# Voltage_Shifters.net
KiCad netlist of a schematic drawn in Altium Designer
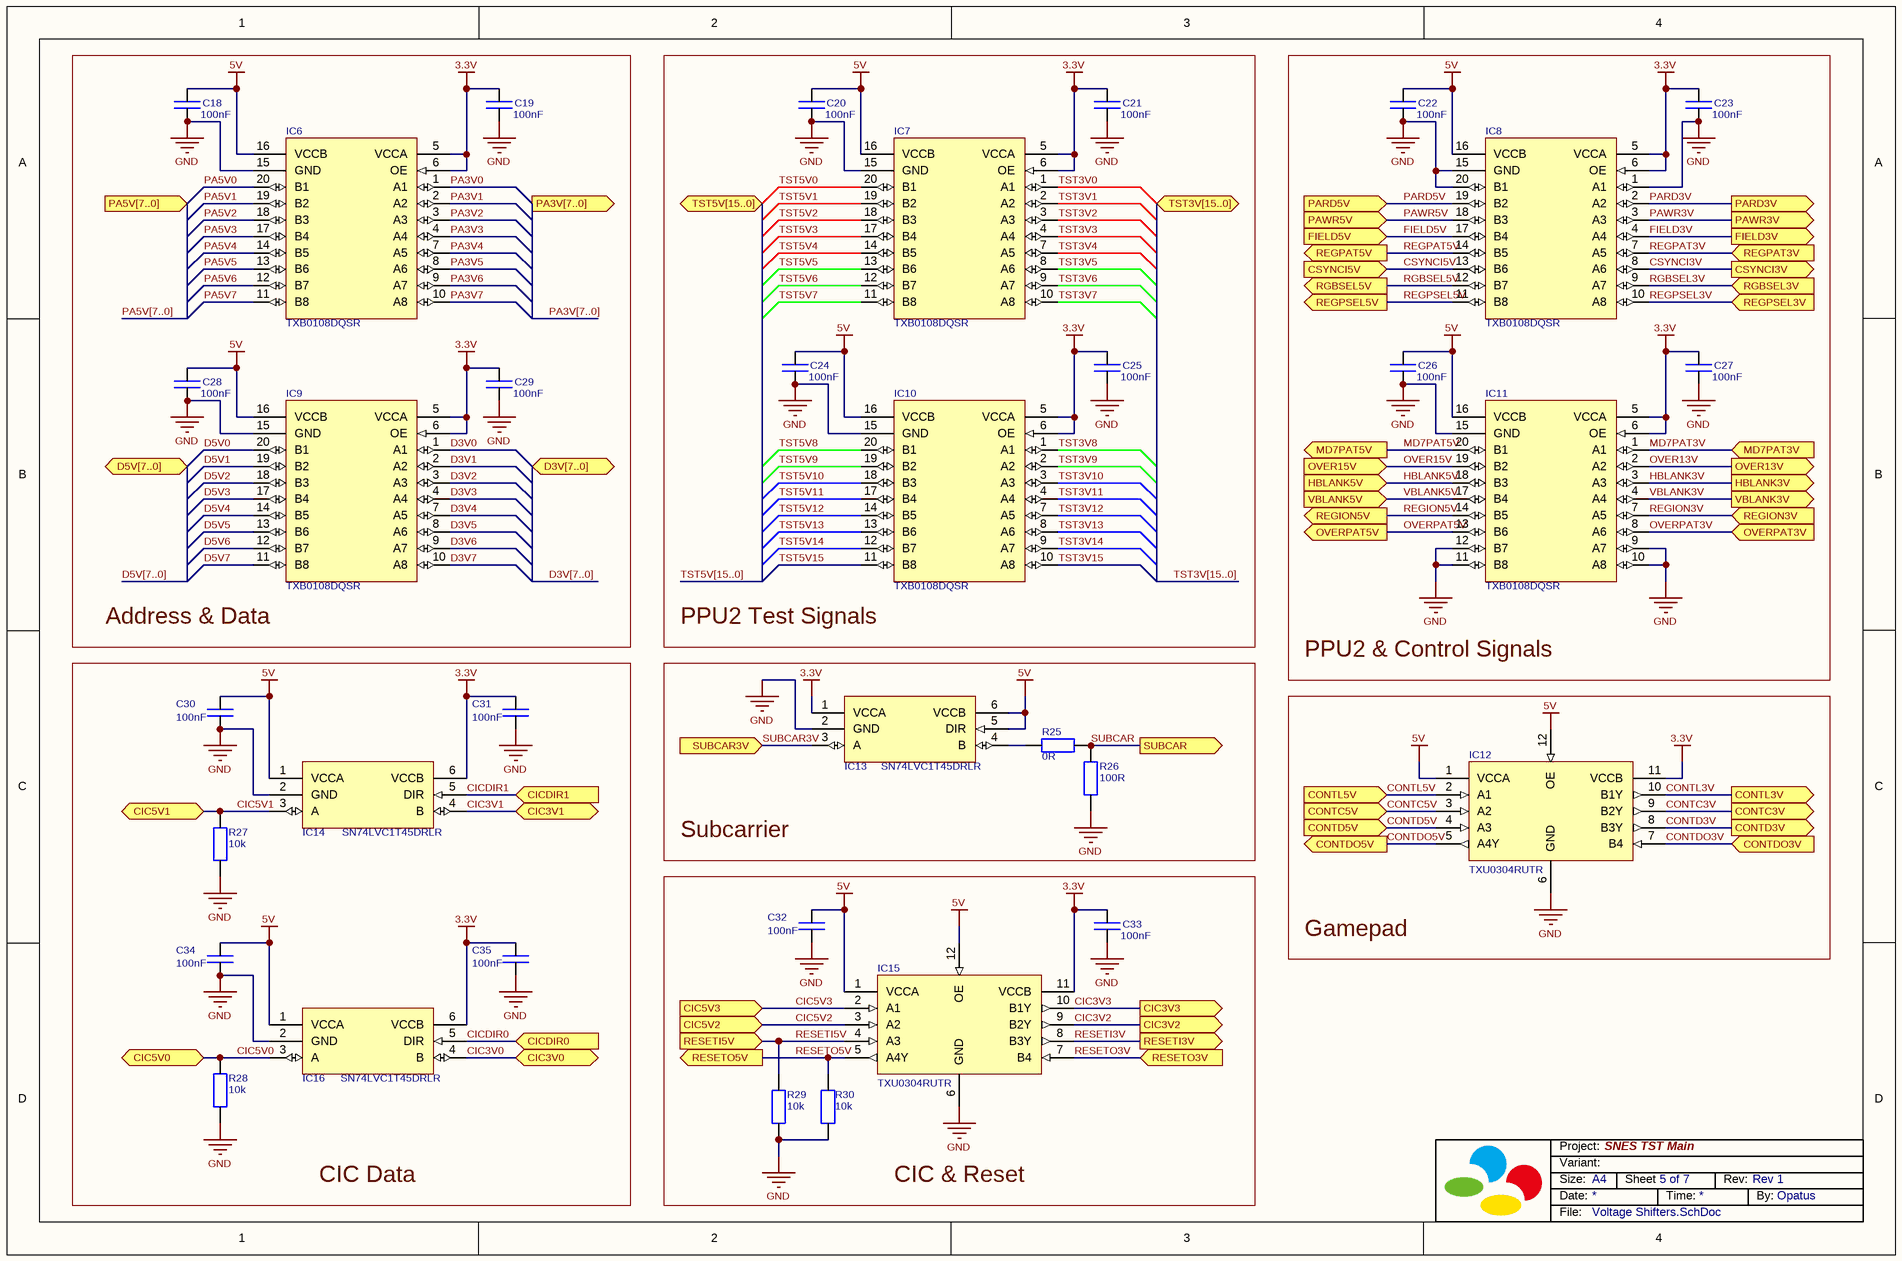
[diagram p0: Voltage Shifters.SchDoc]

(export (version "E")
  (design (tool "Eeschema 10.0.6"))
  (components
    (comp (ref "C18")
      (value "100nF")
      (footprint "Cap_0402_Chip")
      (fields
        (field (name "TOLERANCE") "±20%")
        (field (name "Comment") "Ceramic Capacitor 100nF 10V ±20% X7R 0402")
      )
      (libsource (lib "PCB") (part "Capacitor"))
    )
    (comp (ref "C19")
      (value "100nF")
      (footprint "Cap_0402_Chip")
      (fields
        (field (name "TOLERANCE") "±20%")
        (field (name "Comment") "Ceramic Capacitor 100nF 10V ±20% X7R 0402")
      )
      (libsource (lib "PCB") (part "Capacitor"))
    )
    (comp (ref "C20")
      (value "100nF")
      (footprint "Cap_0402_Chip")
      (fields
        (field (name "TOLERANCE") "±20%")
        (field (name "Comment") "Ceramic Capacitor 100nF 10V ±20% X7R 0402")
      )
      (libsource (lib "PCB") (part "Capacitor"))
    )
    (comp (ref "C21")
      (value "100nF")
      (footprint "Cap_0402_Chip")
      (fields
        (field (name "TOLERANCE") "±20%")
        (field (name "Comment") "Ceramic Capacitor 100nF 10V ±20% X7R 0402")
      )
      (libsource (lib "PCB") (part "Capacitor"))
    )
    (comp (ref "C22")
      (value "100nF")
      (footprint "Cap_0402_Chip")
      (fields
        (field (name "TOLERANCE") "±20%")
        (field (name "Comment") "Ceramic Capacitor 100nF 10V ±20% X7R 0402")
      )
      (libsource (lib "PCB") (part "Capacitor"))
    )
    (comp (ref "C23")
      (value "100nF")
      (footprint "Cap_0402_Chip")
      (fields
        (field (name "TOLERANCE") "±20%")
        (field (name "Comment") "Ceramic Capacitor 100nF 10V ±20% X7R 0402")
      )
      (libsource (lib "PCB") (part "Capacitor"))
    )
    (comp (ref "C24")
      (value "100nF")
      (footprint "Cap_0402_Chip")
      (fields
        (field (name "TOLERANCE") "±20%")
        (field (name "Comment") "Ceramic Capacitor 100nF 10V ±20% X7R 0402")
      )
      (libsource (lib "PCB") (part "Capacitor"))
    )
    (comp (ref "C25")
      (value "100nF")
      (footprint "Cap_0402_Chip")
      (fields
        (field (name "TOLERANCE") "±20%")
        (field (name "Comment") "Ceramic Capacitor 100nF 10V ±20% X7R 0402")
      )
      (libsource (lib "PCB") (part "Capacitor"))
    )
    (comp (ref "C26")
      (value "100nF")
      (footprint "Cap_0402_Chip")
      (fields
        (field (name "TOLERANCE") "±20%")
        (field (name "Comment") "Ceramic Capacitor 100nF 10V ±20% X7R 0402")
      )
      (libsource (lib "PCB") (part "Capacitor"))
    )
    (comp (ref "C27")
      (value "100nF")
      (footprint "Cap_0402_Chip")
      (fields
        (field (name "TOLERANCE") "±20%")
        (field (name "Comment") "Ceramic Capacitor 100nF 10V ±20% X7R 0402")
      )
      (libsource (lib "PCB") (part "Capacitor"))
    )
    (comp (ref "C28")
      (value "100nF")
      (footprint "Cap_0402_Chip")
      (fields
        (field (name "TOLERANCE") "±20%")
        (field (name "Comment") "Ceramic Capacitor 100nF 10V ±20% X7R 0402")
      )
      (libsource (lib "PCB") (part "Capacitor"))
    )
    (comp (ref "C29")
      (value "100nF")
      (footprint "Cap_0402_Chip")
      (fields
        (field (name "TOLERANCE") "±20%")
        (field (name "Comment") "Ceramic Capacitor 100nF 10V ±20% X7R 0402")
      )
      (libsource (lib "PCB") (part "Capacitor"))
    )
    (comp (ref "C30")
      (value "100nF")
      (footprint "Cap_0402_Chip")
      (fields
        (field (name "TOLERANCE") "±20%")
        (field (name "Comment") "Ceramic Capacitor 100nF 10V ±20% X7R 0402")
      )
      (libsource (lib "PCB") (part "Capacitor"))
    )
    (comp (ref "C31")
      (value "100nF")
      (footprint "Cap_0402_Chip")
      (fields
        (field (name "TOLERANCE") "±20%")
        (field (name "Comment") "Ceramic Capacitor 100nF 10V ±20% X7R 0402")
      )
      (libsource (lib "PCB") (part "Capacitor"))
    )
    (comp (ref "C32")
      (value "100nF")
      (footprint "Cap_0402_Chip")
      (fields
        (field (name "TOLERANCE") "±20%")
        (field (name "Comment") "Ceramic Capacitor 100nF 10V ±20% X7R 0402")
      )
      (libsource (lib "PCB") (part "Capacitor"))
    )
    (comp (ref "C33")
      (value "100nF")
      (footprint "Cap_0402_Chip")
      (fields
        (field (name "TOLERANCE") "±20%")
        (field (name "Comment") "Ceramic Capacitor 100nF 10V ±20% X7R 0402")
      )
      (libsource (lib "PCB") (part "Capacitor"))
    )
    (comp (ref "C34")
      (value "100nF")
      (footprint "Cap_0402_Chip")
      (fields
        (field (name "TOLERANCE") "±20%")
        (field (name "Comment") "Ceramic Capacitor 100nF 10V ±20% X7R 0402")
      )
      (libsource (lib "PCB") (part "Capacitor"))
    )
    (comp (ref "C35")
      (value "100nF")
      (footprint "Cap_0402_Chip")
      (fields
        (field (name "TOLERANCE") "±20%")
        (field (name "Comment") "Ceramic Capacitor 100nF 10V ±20% X7R 0402")
      )
      (libsource (lib "PCB") (part "Capacitor"))
    )
    (comp (ref "IC6")
      (value "TXB0108DQSR")
      (footprint "SON20")
      (description "8-bit level shifter")
      (fields
        (field (name "MANUFACTURER") "Texas Instruments")
        (field (name "MANUFACTURER_PART_NUMBER") "TXB0108DQSR")
      )
      (libsource (lib "PCB") (part "TXB0108DQSR"))
    )
    (comp (ref "IC7")
      (value "TXB0108DQSR")
      (footprint "SON20")
      (description "8-bit level shifter")
      (fields
        (field (name "MANUFACTURER") "Texas Instruments")
        (field (name "MANUFACTURER_PART_NUMBER") "TXB0108DQSR")
      )
      (libsource (lib "PCB") (part "TXB0108DQSR"))
    )
    (comp (ref "IC8")
      (value "TXB0108DQSR")
      (footprint "SON20")
      (description "8-bit level shifter")
      (fields
        (field (name "MANUFACTURER") "Texas Instruments")
        (field (name "MANUFACTURER_PART_NUMBER") "TXB0108DQSR")
      )
      (libsource (lib "PCB") (part "TXB0108DQSR"))
    )
    (comp (ref "IC9")
      (value "TXB0108DQSR")
      (footprint "SON20")
      (description "8-bit level shifter")
      (fields
        (field (name "MANUFACTURER") "Texas Instruments")
        (field (name "MANUFACTURER_PART_NUMBER") "TXB0108DQSR")
      )
      (libsource (lib "PCB") (part "TXB0108DQSR"))
    )
    (comp (ref "IC10")
      (value "TXB0108DQSR")
      (footprint "SON20")
      (description "8-bit level shifter")
      (fields
        (field (name "MANUFACTURER") "Texas Instruments")
        (field (name "MANUFACTURER_PART_NUMBER") "TXB0108DQSR")
      )
      (libsource (lib "PCB") (part "TXB0108DQSR"))
    )
    (comp (ref "IC11")
      (value "TXB0108DQSR")
      (footprint "SON20")
      (description "8-bit level shifter")
      (fields
        (field (name "MANUFACTURER") "Texas Instruments")
        (field (name "MANUFACTURER_PART_NUMBER") "TXB0108DQSR")
      )
      (libsource (lib "PCB") (part "TXB0108DQSR"))
    )
    (comp (ref "IC12")
      (value "TXU0304")
      (footprint "UQFN12")
      (description "4-bit level shifter")
      (fields
        (field (name "MANUFACTURER") "Texas Instruments")
        (field (name "MANUFACTURER_PART_NUMBER") "TXU0304RUTR")
      )
      (libsource (lib "PCB") (part "TXU0304"))
    )
    (comp (ref "IC13")
      (value "SN74LVC1T45")
      (footprint "SOT-5X3")
      (description "1-bit Transceiver")
      (fields
        (field (name "MANUFACTURER") "Texas Instruments")
        (field (name "MANUFACTURER_PART_NUMBER") "SN74LVC1T45DRLR")
      )
      (libsource (lib "PCB") (part "SN74LVC1T45"))
    )
    (comp (ref "IC14")
      (value "SN74LVC1T45")
      (footprint "SOT-5X3")
      (description "1-bit Transceiver")
      (fields
        (field (name "MANUFACTURER") "Texas Instruments")
        (field (name "MANUFACTURER_PART_NUMBER") "SN74LVC1T45DRLR")
      )
      (libsource (lib "PCB") (part "SN74LVC1T45"))
    )
    (comp (ref "IC15")
      (value "TXU0304")
      (footprint "UQFN12")
      (description "4-bit level shifter")
      (fields
        (field (name "MANUFACTURER") "Texas Instruments")
        (field (name "MANUFACTURER_PART_NUMBER") "TXU0304RUTR")
      )
      (libsource (lib "PCB") (part "TXU0304"))
    )
    (comp (ref "IC16")
      (value "SN74LVC1T45")
      (footprint "SOT-5X3")
      (description "1-bit Transceiver")
      (fields
        (field (name "MANUFACTURER") "Texas Instruments")
        (field (name "MANUFACTURER_PART_NUMBER") "SN74LVC1T45DRLR")
      )
      (libsource (lib "PCB") (part "SN74LVC1T45"))
    )
    (comp (ref "R25")
      (value "0R")
      (footprint "Res_0603_Chip")
      (fields (field (name "TOLERANCE") "±1%") (field (name "Comment") "Resistor 0R 0603 ±1%"))
      (libsource (lib "") (part "R_2"))
    )
    (comp (ref "R26")
      (value "100R")
      (footprint "Res_0603_Chip")
      (fields (field (name "TOLERANCE") "±1%") (field (name "Comment") "Resistor 100R 0603 ±1%"))
      (libsource (lib "") (part "R_1"))
    )
    (comp (ref "R27")
      (value "10k")
      (footprint "Res_0402_Chip")
      (fields (field (name "TOLERANCE") "±1%") (field (name "Comment") "Resistor 10k 0402 ±1%"))
      (libsource (lib "PCB") (part "R"))
    )
    (comp (ref "R28")
      (value "10k")
      (footprint "Res_0402_Chip")
      (fields (field (name "TOLERANCE") "±1%") (field (name "Comment") "Resistor 10k 0402 ±1%"))
      (libsource (lib "PCB") (part "R"))
    )
    (comp (ref "R29")
      (value "10k")
      (footprint "Res_0402_Chip")
      (fields (field (name "TOLERANCE") "±1%") (field (name "Comment") "Resistor 10k 0402 ±1%"))
      (libsource (lib "") (part "R_1"))
    )
    (comp (ref "R30")
      (value "10k")
      (footprint "Res_0402_Chip")
      (fields (field (name "TOLERANCE") "±1%") (field (name "Comment") "Resistor 10k 0402 ±1%"))
      (libsource (lib "PCB") (part "R"))
    )
  )
  (nets
    (net (code "1") (name "/CIC3V0") (class "Default")
      (node (ref "IC16") (pin "4") (pinfunction "B_4") (pintype "bidirectional"))
    )
    (net (code "2") (name "/CIC3V1") (class "Default")
      (node (ref "IC14") (pin "4") (pinfunction "B_4") (pintype "bidirectional"))
    )
    (net (code "3") (name "/CIC3V2") (class "Default")
      (node (ref "IC15") (pin "9") (pinfunction "B2Y_9") (pintype "output"))
    )
    (net (code "4") (name "/CIC3V3") (class "Default")
      (node (ref "IC15") (pin "10") (pinfunction "B1Y_10") (pintype "output"))
    )
    (net (code "5") (name "/CIC5V0") (class "Default")
      (node (ref "IC16") (pin "3") (pinfunction "A_3") (pintype "bidirectional"))
      (node (ref "R28") (pin "2") (pintype "passive"))
    )
    (net (code "6") (name "/CIC5V1") (class "Default")
      (node (ref "IC14") (pin "3") (pinfunction "A_3") (pintype "bidirectional"))
      (node (ref "R27") (pin "2") (pintype "passive"))
    )
    (net (code "7") (name "/CIC5V2") (class "Default")
      (node (ref "IC15") (pin "3") (pinfunction "A2_3") (pintype "input"))
    )
    (net (code "8") (name "/CIC5V3") (class "Default")
      (node (ref "IC15") (pin "2") (pinfunction "A1_2") (pintype "input"))
    )
    (net (code "9") (name "/CICDIR0") (class "Default")
      (node (ref "IC16") (pin "5") (pinfunction "DIR_5") (pintype "input"))
    )
    (net (code "10") (name "/CICDIR1") (class "Default")
      (node (ref "IC14") (pin "5") (pinfunction "DIR_5") (pintype "input"))
    )
    (net (code "11") (name "/CONTC3V") (class "Default")
      (node (ref "IC12") (pin "9") (pinfunction "B2Y_9") (pintype "output"))
    )
    (net (code "12") (name "/CONTC5V") (class "Default")
      (node (ref "IC12") (pin "3") (pinfunction "A2_3") (pintype "input"))
    )
    (net (code "13") (name "/CONTD3V") (class "Default")
      (node (ref "IC12") (pin "8") (pinfunction "B3Y_8") (pintype "output"))
    )
    (net (code "14") (name "/CONTD5V") (class "Default")
      (node (ref "IC12") (pin "4") (pinfunction "A3_4") (pintype "input"))
    )
    (net (code "15") (name "/CONTDO3V") (class "Default")
      (node (ref "IC12") (pin "7") (pinfunction "B4_7") (pintype "input"))
    )
    (net (code "16") (name "/CONTDO5V") (class "Default")
      (node (ref "IC12") (pin "5") (pinfunction "A4Y_5") (pintype "output"))
    )
    (net (code "17") (name "/CONTL3V") (class "Default")
      (node (ref "IC12") (pin "10") (pinfunction "B1Y_10") (pintype "output"))
    )
    (net (code "18") (name "/CONTL5V") (class "Default")
      (node (ref "IC12") (pin "2") (pinfunction "A1_2") (pintype "input"))
    )
    (net (code "19") (name "/CSYNCI3V") (class "Default")
      (node (ref "IC8") (pin "8") (pinfunction "A6_8") (pintype "bidirectional"))
    )
    (net (code "20") (name "/CSYNCI5V") (class "Default")
      (node (ref "IC8") (pin "13") (pinfunction "B6_13") (pintype "bidirectional"))
    )
    (net (code "21") (name "/D3V0") (class "Default")
      (node (ref "IC9") (pin "1") (pinfunction "A1_1") (pintype "bidirectional"))
    )
    (net (code "22") (name "/D3V1") (class "Default")
      (node (ref "IC9") (pin "2") (pinfunction "A2_2") (pintype "bidirectional"))
    )
    (net (code "23") (name "/D3V2") (class "Default")
      (node (ref "IC9") (pin "3") (pinfunction "A3_3") (pintype "bidirectional"))
    )
    (net (code "24") (name "/D3V3") (class "Default")
      (node (ref "IC9") (pin "4") (pinfunction "A4_4") (pintype "bidirectional"))
    )
    (net (code "25") (name "/D3V4") (class "Default")
      (node (ref "IC9") (pin "7") (pinfunction "A5_7") (pintype "bidirectional"))
    )
    (net (code "26") (name "/D3V5") (class "Default")
      (node (ref "IC9") (pin "8") (pinfunction "A6_8") (pintype "bidirectional"))
    )
    (net (code "27") (name "/D3V6") (class "Default")
      (node (ref "IC9") (pin "9") (pinfunction "A7_9") (pintype "bidirectional"))
    )
    (net (code "28") (name "/D3V7") (class "Default")
      (node (ref "IC9") (pin "10") (pinfunction "A8_10") (pintype "bidirectional"))
    )
    (net (code "30") (name "/D5V0") (class "Default")
      (node (ref "IC9") (pin "20") (pinfunction "B1_20") (pintype "bidirectional"))
    )
    (net (code "31") (name "/D5V1") (class "Default")
      (node (ref "IC9") (pin "19") (pinfunction "B2_19") (pintype "bidirectional"))
    )
    (net (code "32") (name "/D5V2") (class "Default")
      (node (ref "IC9") (pin "18") (pinfunction "B3_18") (pintype "bidirectional"))
    )
    (net (code "33") (name "/D5V3") (class "Default")
      (node (ref "IC9") (pin "17") (pinfunction "B4_17") (pintype "bidirectional"))
    )
    (net (code "34") (name "/D5V4") (class "Default")
      (node (ref "IC9") (pin "14") (pinfunction "B5_14") (pintype "bidirectional"))
    )
    (net (code "35") (name "/D5V5") (class "Default")
      (node (ref "IC9") (pin "13") (pinfunction "B6_13") (pintype "bidirectional"))
    )
    (net (code "36") (name "/D5V6") (class "Default")
      (node (ref "IC9") (pin "12") (pinfunction "B7_12") (pintype "bidirectional"))
    )
    (net (code "37") (name "/D5V7") (class "Default")
      (node (ref "IC9") (pin "11") (pinfunction "B8_11") (pintype "bidirectional"))
    )
    (net (code "39") (name "/FIELD3V") (class "Default")
      (node (ref "IC8") (pin "4") (pinfunction "A4_4") (pintype "bidirectional"))
    )
    (net (code "40") (name "/FIELD5V") (class "Default")
      (node (ref "IC8") (pin "17") (pinfunction "B4_17") (pintype "bidirectional"))
    )
    (net (code "41") (name "/HBLANK3V") (class "Default")
      (node (ref "IC11") (pin "3") (pinfunction "A3_3") (pintype "bidirectional"))
    )
    (net (code "42") (name "/HBLANK5V") (class "Default")
      (node (ref "IC11") (pin "18") (pinfunction "B3_18") (pintype "bidirectional"))
    )
    (net (code "43") (name "/MD7PAT3V") (class "Default")
      (node (ref "IC11") (pin "1") (pinfunction "A1_1") (pintype "bidirectional"))
    )
    (net (code "44") (name "/MD7PAT5V") (class "Default")
      (node (ref "IC11") (pin "20") (pinfunction "B1_20") (pintype "bidirectional"))
    )
    (net (code "45") (name "/OVER13V") (class "Default")
      (node (ref "IC11") (pin "2") (pinfunction "A2_2") (pintype "bidirectional"))
    )
    (net (code "46") (name "/OVER15V") (class "Default")
      (node (ref "IC11") (pin "19") (pinfunction "B2_19") (pintype "bidirectional"))
    )
    (net (code "47") (name "/OVERPAT3V") (class "Default")
      (node (ref "IC11") (pin "8") (pinfunction "A6_8") (pintype "bidirectional"))
    )
    (net (code "48") (name "/OVERPAT5V") (class "Default")
      (node (ref "IC11") (pin "13") (pinfunction "B6_13") (pintype "bidirectional"))
    )
    (net (code "49") (name "/PA3V0") (class "Default")
      (node (ref "IC6") (pin "1") (pinfunction "A1_1") (pintype "bidirectional"))
    )
    (net (code "50") (name "/PA3V1") (class "Default")
      (node (ref "IC6") (pin "2") (pinfunction "A2_2") (pintype "bidirectional"))
    )
    (net (code "51") (name "/PA3V2") (class "Default")
      (node (ref "IC6") (pin "3") (pinfunction "A3_3") (pintype "bidirectional"))
    )
    (net (code "52") (name "/PA3V3") (class "Default")
      (node (ref "IC6") (pin "4") (pinfunction "A4_4") (pintype "bidirectional"))
    )
    (net (code "53") (name "/PA3V4") (class "Default")
      (node (ref "IC6") (pin "7") (pinfunction "A5_7") (pintype "bidirectional"))
    )
    (net (code "54") (name "/PA3V5") (class "Default")
      (node (ref "IC6") (pin "8") (pinfunction "A6_8") (pintype "bidirectional"))
    )
    (net (code "55") (name "/PA3V6") (class "Default")
      (node (ref "IC6") (pin "9") (pinfunction "A7_9") (pintype "bidirectional"))
    )
    (net (code "56") (name "/PA3V7") (class "Default")
      (node (ref "IC6") (pin "10") (pinfunction "A8_10") (pintype "bidirectional"))
    )
    (net (code "58") (name "/PA5V0") (class "Default")
      (node (ref "IC6") (pin "20") (pinfunction "B1_20") (pintype "bidirectional"))
    )
    (net (code "59") (name "/PA5V1") (class "Default")
      (node (ref "IC6") (pin "19") (pinfunction "B2_19") (pintype "bidirectional"))
    )
    (net (code "60") (name "/PA5V2") (class "Default")
      (node (ref "IC6") (pin "18") (pinfunction "B3_18") (pintype "bidirectional"))
    )
    (net (code "61") (name "/PA5V3") (class "Default")
      (node (ref "IC6") (pin "17") (pinfunction "B4_17") (pintype "bidirectional"))
    )
    (net (code "62") (name "/PA5V4") (class "Default")
      (node (ref "IC6") (pin "14") (pinfunction "B5_14") (pintype "bidirectional"))
    )
    (net (code "63") (name "/PA5V5") (class "Default")
      (node (ref "IC6") (pin "13") (pinfunction "B6_13") (pintype "bidirectional"))
    )
    (net (code "64") (name "/PA5V6") (class "Default")
      (node (ref "IC6") (pin "12") (pinfunction "B7_12") (pintype "bidirectional"))
    )
    (net (code "65") (name "/PA5V7") (class "Default")
      (node (ref "IC6") (pin "11") (pinfunction "B8_11") (pintype "bidirectional"))
    )
    (net (code "67") (name "/PARD3V") (class "Default")
      (node (ref "IC8") (pin "2") (pinfunction "A2_2") (pintype "bidirectional"))
    )
    (net (code "68") (name "/PARD5V") (class "Default")
      (node (ref "IC8") (pin "19") (pinfunction "B2_19") (pintype "bidirectional"))
    )
    (net (code "69") (name "/PAWR3V") (class "Default")
      (node (ref "IC8") (pin "3") (pinfunction "A3_3") (pintype "bidirectional"))
    )
    (net (code "70") (name "/PAWR5V") (class "Default")
      (node (ref "IC8") (pin "18") (pinfunction "B3_18") (pintype "bidirectional"))
    )
    (net (code "71") (name "/REGION3V") (class "Default")
      (node (ref "IC11") (pin "7") (pinfunction "A5_7") (pintype "bidirectional"))
    )
    (net (code "72") (name "/REGION5V") (class "Default")
      (node (ref "IC11") (pin "14") (pinfunction "B5_14") (pintype "bidirectional"))
    )
    (net (code "73") (name "/REGPAT3V") (class "Default")
      (node (ref "IC8") (pin "7") (pinfunction "A5_7") (pintype "bidirectional"))
    )
    (net (code "74") (name "/REGPAT5V") (class "Default")
      (node (ref "IC8") (pin "14") (pinfunction "B5_14") (pintype "bidirectional"))
    )
    (net (code "75") (name "/REGPSEL3V") (class "Default")
      (node (ref "IC8") (pin "10") (pinfunction "A8_10") (pintype "bidirectional"))
    )
    (net (code "76") (name "/REGPSEL5V") (class "Default")
      (node (ref "IC8") (pin "11") (pinfunction "B8_11") (pintype "bidirectional"))
    )
    (net (code "77") (name "/RESETI3V") (class "Default")
      (node (ref "IC15") (pin "8") (pinfunction "B3Y_8") (pintype "output"))
    )
    (net (code "78") (name "/RESETI5V") (class "Default")
      (node (ref "IC15") (pin "4") (pinfunction "A3_4") (pintype "input"))
      (node (ref "R29") (pin "1") (pintype "passive"))
    )
    (net (code "79") (name "/RESETO3V") (class "Default")
      (node (ref "IC15") (pin "7") (pinfunction "B4_7") (pintype "input"))
    )
    (net (code "80") (name "/RESETO5V") (class "Default")
      (node (ref "IC15") (pin "5") (pinfunction "A4Y_5") (pintype "output"))
      (node (ref "R30") (pin "2") (pintype "passive"))
    )
    (net (code "81") (name "/RGBSEL3V") (class "Default")
      (node (ref "IC8") (pin "9") (pinfunction "A7_9") (pintype "bidirectional"))
    )
    (net (code "82") (name "/RGBSEL5V") (class "Default")
      (node (ref "IC8") (pin "12") (pinfunction "B7_12") (pintype "bidirectional"))
    )
    (net (code "83") (name "/SUBCAR") (class "Default")
      (node (ref "R25") (pin "1") (pintype "passive"))
      (node (ref "R26") (pin "1") (pintype "passive"))
    )
    (net (code "84") (name "/SUBCAR3V") (class "Default")
      (node (ref "IC13") (pin "3") (pinfunction "A_3") (pintype "bidirectional"))
    )
    (net (code "85") (name "/TST3V0") (class "Default")
      (node (ref "IC7") (pin "1") (pinfunction "A1_1") (pintype "bidirectional"))
    )
    (net (code "86") (name "/TST3V1") (class "Default")
      (node (ref "IC7") (pin "2") (pinfunction "A2_2") (pintype "bidirectional"))
    )
    (net (code "87") (name "/TST3V2") (class "Default")
      (node (ref "IC7") (pin "3") (pinfunction "A3_3") (pintype "bidirectional"))
    )
    (net (code "88") (name "/TST3V3") (class "Default")
      (node (ref "IC7") (pin "4") (pinfunction "A4_4") (pintype "bidirectional"))
    )
    (net (code "89") (name "/TST3V4") (class "Default")
      (node (ref "IC7") (pin "7") (pinfunction "A5_7") (pintype "bidirectional"))
    )
    (net (code "90") (name "/TST3V5") (class "Default")
      (node (ref "IC7") (pin "8") (pinfunction "A6_8") (pintype "bidirectional"))
    )
    (net (code "91") (name "/TST3V6") (class "Default")
      (node (ref "IC7") (pin "9") (pinfunction "A7_9") (pintype "bidirectional"))
    )
    (net (code "92") (name "/TST3V7") (class "Default")
      (node (ref "IC7") (pin "10") (pinfunction "A8_10") (pintype "bidirectional"))
    )
    (net (code "93") (name "/TST3V8") (class "Default")
      (node (ref "IC10") (pin "1") (pinfunction "A1_1") (pintype "bidirectional"))
    )
    (net (code "94") (name "/TST3V9") (class "Default")
      (node (ref "IC10") (pin "2") (pinfunction "A2_2") (pintype "bidirectional"))
    )
    (net (code "95") (name "/TST3V10") (class "Default")
      (node (ref "IC10") (pin "3") (pinfunction "A3_3") (pintype "bidirectional"))
    )
    (net (code "96") (name "/TST3V11") (class "Default")
      (node (ref "IC10") (pin "4") (pinfunction "A4_4") (pintype "bidirectional"))
    )
    (net (code "97") (name "/TST3V12") (class "Default")
      (node (ref "IC10") (pin "7") (pinfunction "A5_7") (pintype "bidirectional"))
    )
    (net (code "98") (name "/TST3V13") (class "Default")
      (node (ref "IC10") (pin "8") (pinfunction "A6_8") (pintype "bidirectional"))
    )
    (net (code "99") (name "/TST3V14") (class "Default")
      (node (ref "IC10") (pin "9") (pinfunction "A7_9") (pintype "bidirectional"))
    )
    (net (code "100") (name "/TST3V15") (class "Default")
      (node (ref "IC10") (pin "10") (pinfunction "A8_10") (pintype "bidirectional"))
    )
    (net (code "102") (name "/TST5V0") (class "Default")
      (node (ref "IC7") (pin "20") (pinfunction "B1_20") (pintype "bidirectional"))
    )
    (net (code "103") (name "/TST5V1") (class "Default")
      (node (ref "IC7") (pin "19") (pinfunction "B2_19") (pintype "bidirectional"))
    )
    (net (code "104") (name "/TST5V2") (class "Default")
      (node (ref "IC7") (pin "18") (pinfunction "B3_18") (pintype "bidirectional"))
    )
    (net (code "105") (name "/TST5V3") (class "Default")
      (node (ref "IC7") (pin "17") (pinfunction "B4_17") (pintype "bidirectional"))
    )
    (net (code "106") (name "/TST5V4") (class "Default")
      (node (ref "IC7") (pin "14") (pinfunction "B5_14") (pintype "bidirectional"))
    )
    (net (code "107") (name "/TST5V5") (class "Default")
      (node (ref "IC7") (pin "13") (pinfunction "B6_13") (pintype "bidirectional"))
    )
    (net (code "108") (name "/TST5V6") (class "Default")
      (node (ref "IC7") (pin "12") (pinfunction "B7_12") (pintype "bidirectional"))
    )
    (net (code "109") (name "/TST5V7") (class "Default")
      (node (ref "IC7") (pin "11") (pinfunction "B8_11") (pintype "bidirectional"))
    )
    (net (code "110") (name "/TST5V8") (class "Default")
      (node (ref "IC10") (pin "20") (pinfunction "B1_20") (pintype "bidirectional"))
    )
    (net (code "111") (name "/TST5V9") (class "Default")
      (node (ref "IC10") (pin "19") (pinfunction "B2_19") (pintype "bidirectional"))
    )
    (net (code "112") (name "/TST5V10") (class "Default")
      (node (ref "IC10") (pin "18") (pinfunction "B3_18") (pintype "bidirectional"))
    )
    (net (code "113") (name "/TST5V11") (class "Default")
      (node (ref "IC10") (pin "17") (pinfunction "B4_17") (pintype "bidirectional"))
    )
    (net (code "114") (name "/TST5V12") (class "Default")
      (node (ref "IC10") (pin "14") (pinfunction "B5_14") (pintype "bidirectional"))
    )
    (net (code "115") (name "/TST5V13") (class "Default")
      (node (ref "IC10") (pin "13") (pinfunction "B6_13") (pintype "bidirectional"))
    )
    (net (code "116") (name "/TST5V14") (class "Default")
      (node (ref "IC10") (pin "12") (pinfunction "B7_12") (pintype "bidirectional"))
    )
    (net (code "117") (name "/TST5V15") (class "Default")
      (node (ref "IC10") (pin "11") (pinfunction "B8_11") (pintype "bidirectional"))
    )
    (net (code "119") (name "/VBLANK3V") (class "Default")
      (node (ref "IC11") (pin "4") (pinfunction "A4_4") (pintype "bidirectional"))
    )
    (net (code "120") (name "/VBLANK5V") (class "Default")
      (node (ref "IC11") (pin "17") (pinfunction "B4_17") (pintype "bidirectional"))
    )
    (net (code "121") (name "3.3V") (class "Default")
      (node (ref "C19") (pin "1") (pintype "passive"))
      (node (ref "C21") (pin "1") (pintype "passive"))
      (node (ref "C23") (pin "1") (pintype "passive"))
      (node (ref "C25") (pin "1") (pintype "passive"))
      (node (ref "C27") (pin "1") (pintype "passive"))
      (node (ref "C29") (pin "1") (pintype "passive"))
      (node (ref "C31") (pin "1") (pintype "passive"))
      (node (ref "C33") (pin "1") (pintype "passive"))
      (node (ref "C35") (pin "1") (pintype "passive"))
      (node (ref "IC10") (pin "5") (pinfunction "VCCA_5") (pintype "power_in"))
      (node (ref "IC10") (pin "6") (pinfunction "OE_6") (pintype "input"))
      (node (ref "IC11") (pin "5") (pinfunction "VCCA_5") (pintype "power_in"))
      (node (ref "IC11") (pin "6") (pinfunction "OE_6") (pintype "input"))
      (node (ref "IC12") (pin "11") (pinfunction "VCCB_11") (pintype "power_in"))
      (node (ref "IC13") (pin "1") (pinfunction "VCCA_1") (pintype "power_in"))
      (node (ref "IC14") (pin "6") (pinfunction "VCCB_6") (pintype "power_in"))
      (node (ref "IC15") (pin "11") (pinfunction "VCCB_11") (pintype "power_in"))
      (node (ref "IC16") (pin "6") (pinfunction "VCCB_6") (pintype "power_in"))
      (node (ref "IC6") (pin "5") (pinfunction "VCCA_5") (pintype "power_in"))
      (node (ref "IC6") (pin "6") (pinfunction "OE_6") (pintype "input"))
      (node (ref "IC7") (pin "5") (pinfunction "VCCA_5") (pintype "power_in"))
      (node (ref "IC7") (pin "6") (pinfunction "OE_6") (pintype "input"))
      (node (ref "IC8") (pin "5") (pinfunction "VCCA_5") (pintype "power_in"))
      (node (ref "IC8") (pin "6") (pinfunction "OE_6") (pintype "input"))
      (node (ref "IC9") (pin "5") (pinfunction "VCCA_5") (pintype "power_in"))
      (node (ref "IC9") (pin "6") (pinfunction "OE_6") (pintype "input"))
    )
    (net (code "122") (name "5V") (class "Default")
      (node (ref "C18") (pin "1") (pintype "passive"))
      (node (ref "C20") (pin "1") (pintype "passive"))
      (node (ref "C22") (pin "1") (pintype "passive"))
      (node (ref "C24") (pin "1") (pintype "passive"))
      (node (ref "C26") (pin "1") (pintype "passive"))
      (node (ref "C28") (pin "1") (pintype "passive"))
      (node (ref "C30") (pin "1") (pintype "passive"))
      (node (ref "C32") (pin "1") (pintype "passive"))
      (node (ref "C34") (pin "1") (pintype "passive"))
      (node (ref "IC10") (pin "16") (pinfunction "VCCB_16") (pintype "power_in"))
      (node (ref "IC11") (pin "16") (pinfunction "VCCB_16") (pintype "power_in"))
      (node (ref "IC12") (pin "1") (pinfunction "VCCA_1") (pintype "power_in"))
      (node (ref "IC12") (pin "12") (pinfunction "OE_12") (pintype "input"))
      (node (ref "IC13") (pin "5") (pinfunction "DIR_5") (pintype "input"))
      (node (ref "IC13") (pin "6") (pinfunction "VCCB_6") (pintype "power_in"))
      (node (ref "IC14") (pin "1") (pinfunction "VCCA_1") (pintype "power_in"))
      (node (ref "IC15") (pin "1") (pinfunction "VCCA_1") (pintype "power_in"))
      (node (ref "IC15") (pin "12") (pinfunction "OE_12") (pintype "input"))
      (node (ref "IC16") (pin "1") (pinfunction "VCCA_1") (pintype "power_in"))
      (node (ref "IC6") (pin "16") (pinfunction "VCCB_16") (pintype "power_in"))
      (node (ref "IC7") (pin "16") (pinfunction "VCCB_16") (pintype "power_in"))
      (node (ref "IC8") (pin "16") (pinfunction "VCCB_16") (pintype "power_in"))
      (node (ref "IC9") (pin "16") (pinfunction "VCCB_16") (pintype "power_in"))
    )
    (net (code "123") (name "GND") (class "Default")
      (node (ref "C18") (pin "2") (pintype "passive"))
      (node (ref "C19") (pin "2") (pintype "passive"))
      (node (ref "C20") (pin "2") (pintype "passive"))
      (node (ref "C21") (pin "2") (pintype "passive"))
      (node (ref "C22") (pin "2") (pintype "passive"))
      (node (ref "C23") (pin "2") (pintype "passive"))
      (node (ref "C24") (pin "2") (pintype "passive"))
      (node (ref "C25") (pin "2") (pintype "passive"))
      (node (ref "C26") (pin "2") (pintype "passive"))
      (node (ref "C27") (pin "2") (pintype "passive"))
      (node (ref "C28") (pin "2") (pintype "passive"))
      (node (ref "C29") (pin "2") (pintype "passive"))
      (node (ref "C30") (pin "2") (pintype "passive"))
      (node (ref "C31") (pin "2") (pintype "passive"))
      (node (ref "C32") (pin "2") (pintype "passive"))
      (node (ref "C33") (pin "2") (pintype "passive"))
      (node (ref "C34") (pin "2") (pintype "passive"))
      (node (ref "C35") (pin "2") (pintype "passive"))
      (node (ref "IC10") (pin "15") (pinfunction "GND_15") (pintype "power_in"))
      (node (ref "IC11") (pin "10") (pinfunction "A8_10") (pintype "bidirectional"))
      (node (ref "IC11") (pin "11") (pinfunction "B8_11") (pintype "bidirectional"))
      (node (ref "IC11") (pin "12") (pinfunction "B7_12") (pintype "bidirectional"))
      (node (ref "IC11") (pin "15") (pinfunction "GND_15") (pintype "power_in"))
      (node (ref "IC11") (pin "9") (pinfunction "A7_9") (pintype "bidirectional"))
      (node (ref "IC12") (pin "6") (pinfunction "GND_6") (pintype "power_in"))
      (node (ref "IC13") (pin "2") (pinfunction "GND_2") (pintype "power_in"))
      (node (ref "IC14") (pin "2") (pinfunction "GND_2") (pintype "power_in"))
      (node (ref "IC15") (pin "6") (pinfunction "GND_6") (pintype "power_in"))
      (node (ref "IC16") (pin "2") (pinfunction "GND_2") (pintype "power_in"))
      (node (ref "IC6") (pin "15") (pinfunction "GND_15") (pintype "power_in"))
      (node (ref "IC7") (pin "15") (pinfunction "GND_15") (pintype "power_in"))
      (node (ref "IC8") (pin "1") (pinfunction "A1_1") (pintype "bidirectional"))
      (node (ref "IC8") (pin "15") (pinfunction "GND_15") (pintype "power_in"))
      (node (ref "IC8") (pin "20") (pinfunction "B1_20") (pintype "bidirectional"))
      (node (ref "IC9") (pin "15") (pinfunction "GND_15") (pintype "power_in"))
      (node (ref "R26") (pin "2") (pintype "passive"))
      (node (ref "R27") (pin "1") (pintype "passive"))
      (node (ref "R28") (pin "1") (pintype "passive"))
      (node (ref "R29") (pin "2") (pintype "passive"))
      (node (ref "R30") (pin "1") (pintype "passive"))
    )
    (net (code "124") (name "Net-(IC13-B)") (class "Default")
      (node (ref "IC13") (pin "4") (pinfunction "B_4") (pintype "bidirectional"))
      (node (ref "R25") (pin "2") (pintype "passive"))
    )
  )
)
